# pfc-control-board.net
KiCad netlist of a schematic drawn in Altium Designer
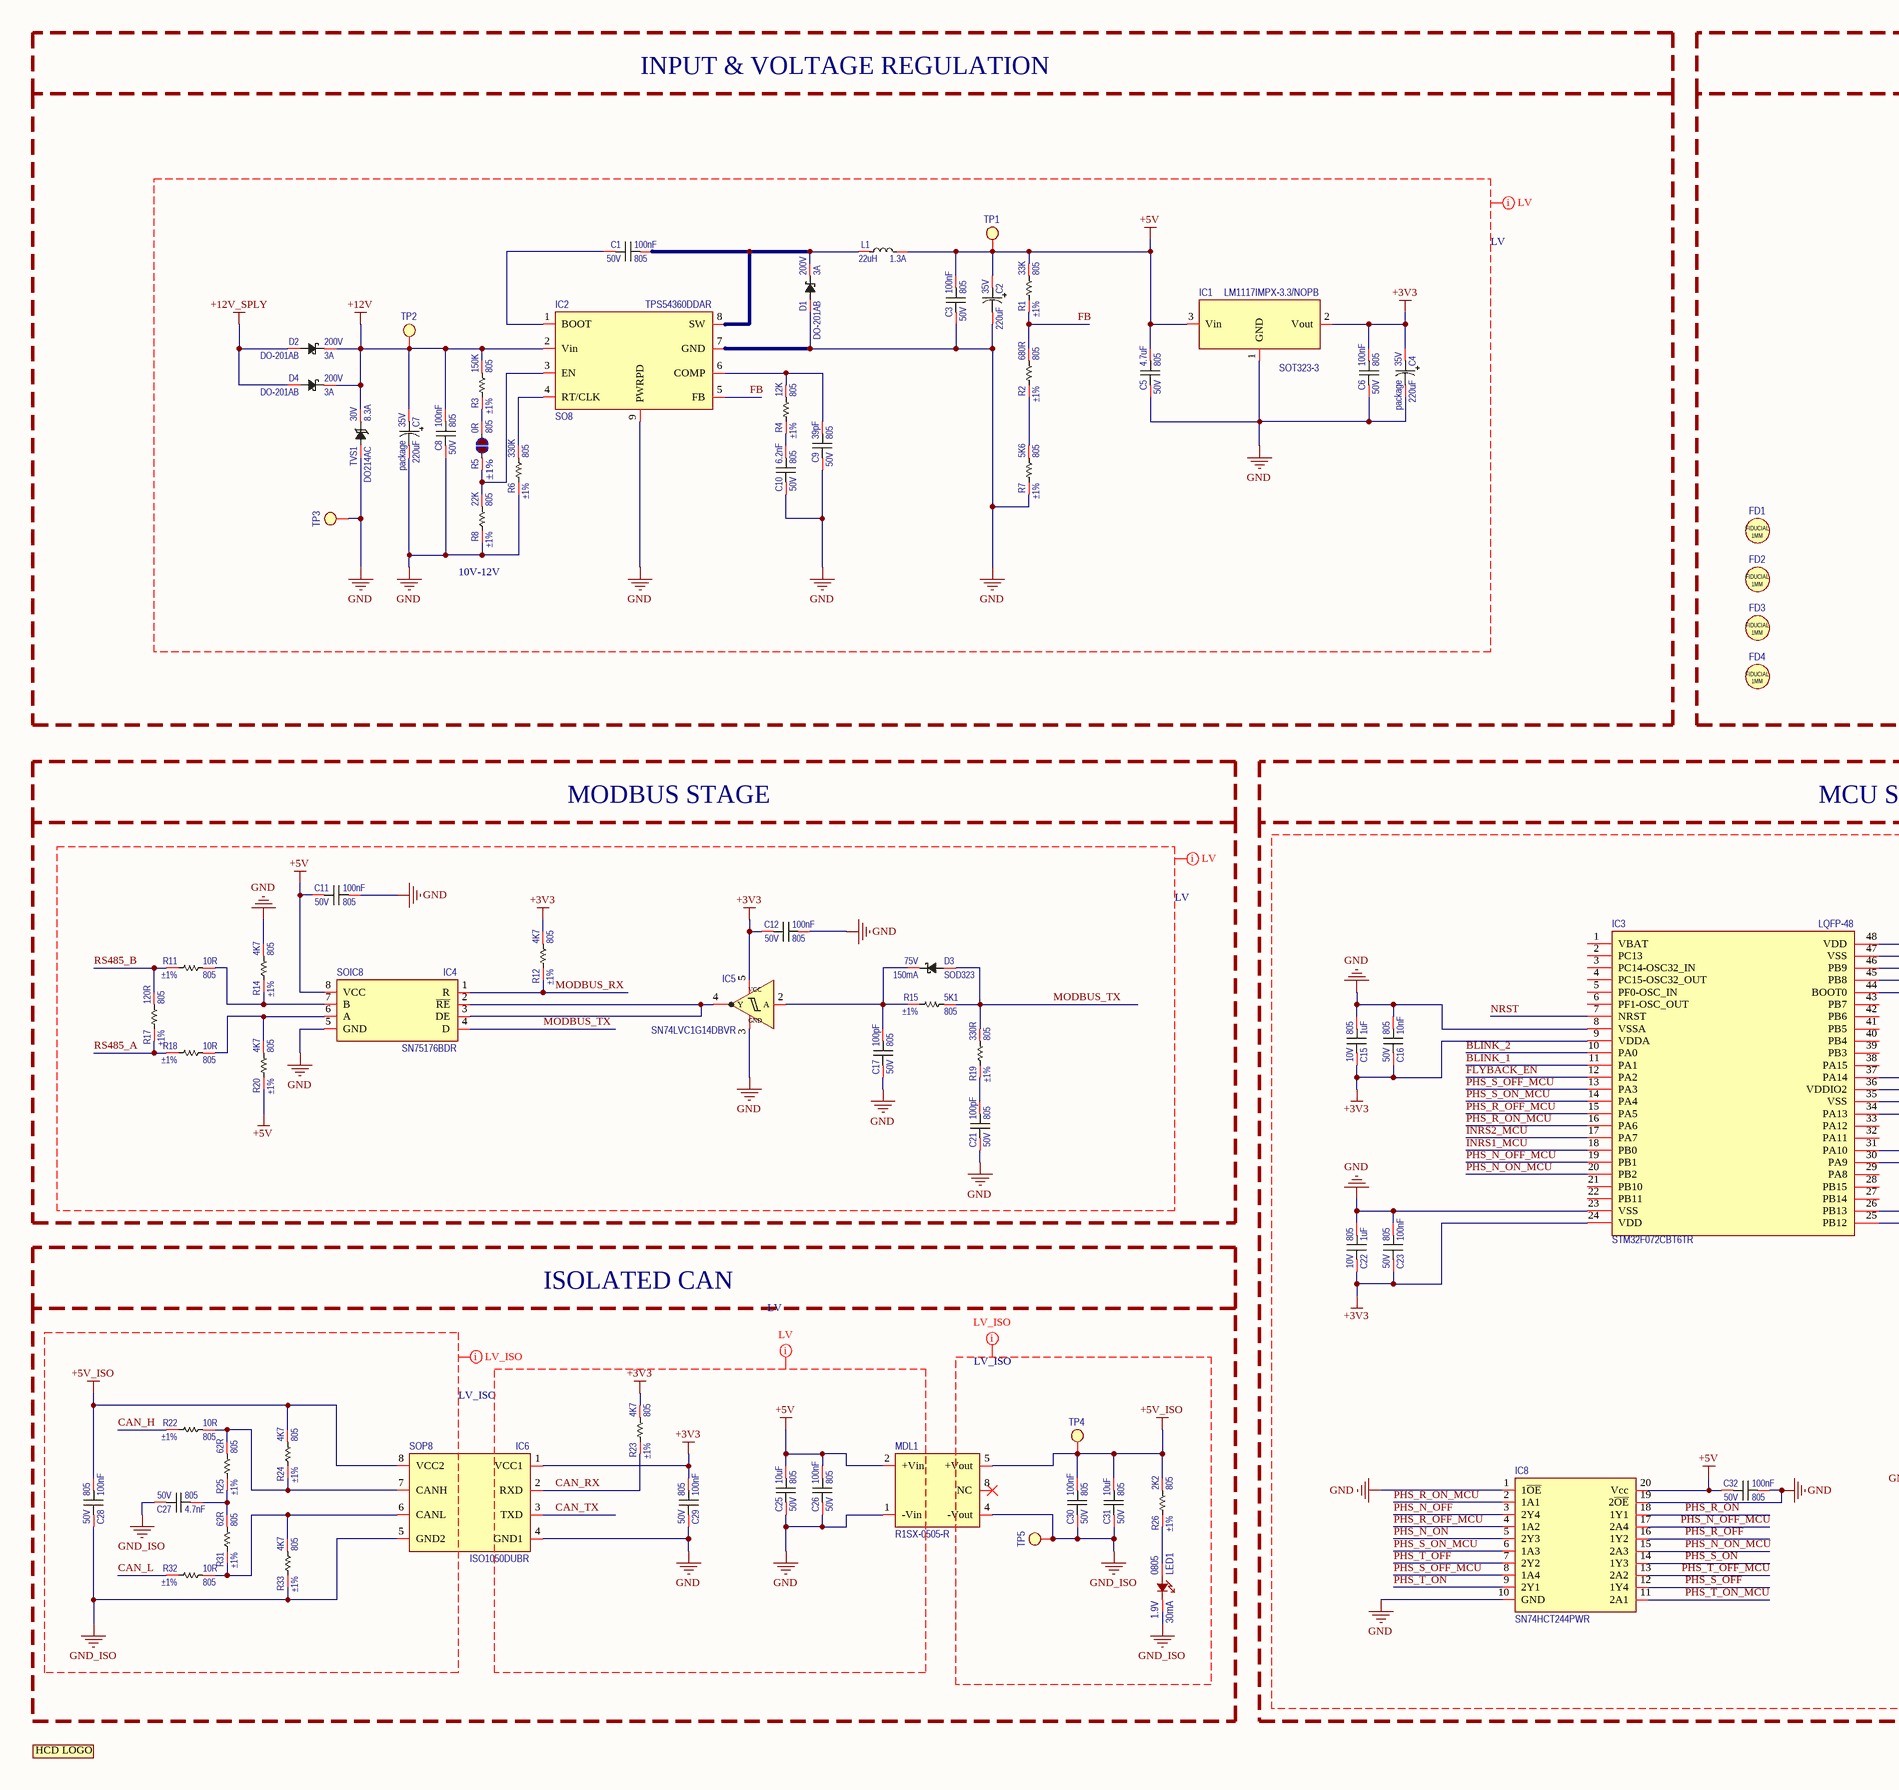
[diagram p0: pfc-control-board.SchDoc, left]
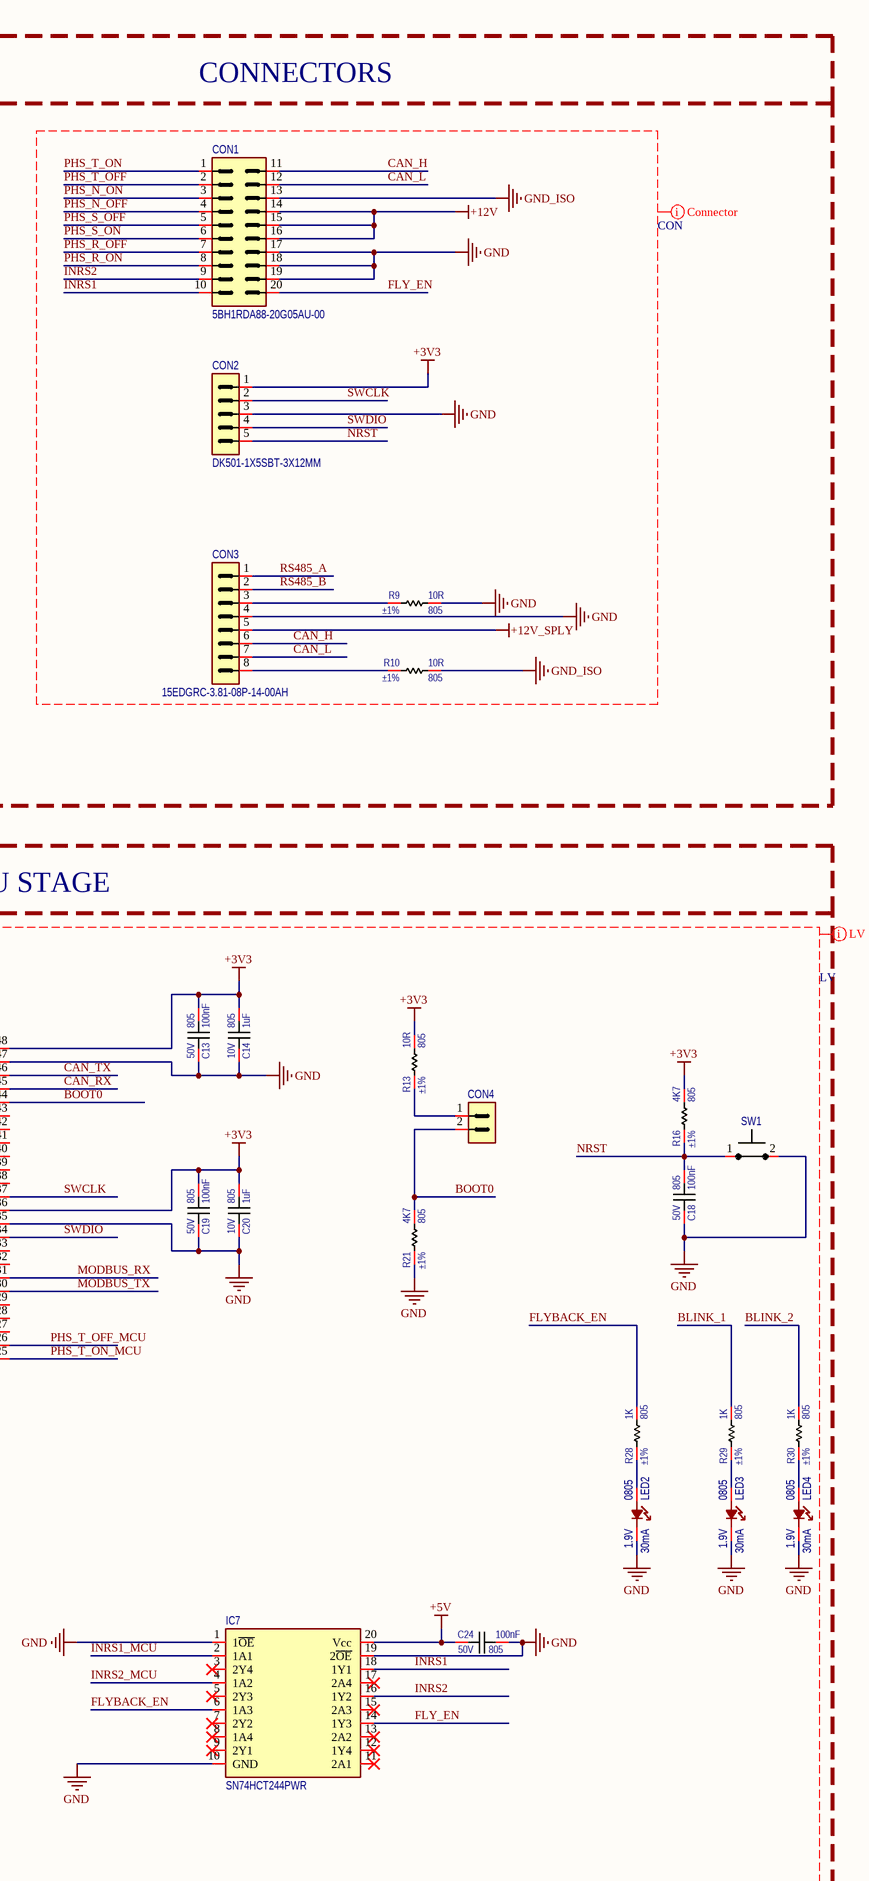
[diagram p1: pfc-control-board.SchDoc, right]

(export (version "E")
  (design (tool "Eeschema 10.0.6"))
  (components
    (comp (ref "C1")
      (value "100nF")
      (footprint "C_0805_L")
      (description "0.1 µF ±20% 50V Ceramic Capacitor X7R 0805 (2012 Metric)")
      (fields
        (field (name "VOLTAGE") "50V")
        (field (name "PACKAGE") "805")
        (field (name "TOLERANCE") "±20%")
        (field (name "MANUFACTURER") "KEMET")
      )
      (libsource (lib "HCD_Database_Libs") (part "StandardCapacitor"))
    )
    (comp (ref "C2")
      (value "220uF")
      (footprint "C_BDS35VC220MH10TP")
      (description "CAP.EL.220uF 35V 8x10 105C 2000Hrs SMD")
      (fields
        (field (name "VOLTAGE") "35V")
        (field (name "MANUFACTURER") "SAMYOUNG")
        (field (name "TOLERANCE") "±20%")
      )
      (libsource (lib "HCD_Database_Libs") (part "PolarizedCapacitor"))
    )
    (comp (ref "C3")
      (value "100nF")
      (footprint "C_0805_L")
      (description "0.1 µF ±20% 50V Ceramic Capacitor X7R 0805 (2012 Metric)")
      (fields
        (field (name "VOLTAGE") "50V")
        (field (name "PACKAGE") "805")
        (field (name "TOLERANCE") "±20%")
        (field (name "MANUFACTURER") "KEMET")
      )
      (libsource (lib "HCD_Database_Libs") (part "StandardCapacitor"))
    )
    (comp (ref "C4")
      (value "220uF")
      (footprint "C_BDS35VC220MH10TP")
      (description "CAP.EL.220uF 35V 8x10 105C 2000Hrs SMD")
      (fields
        (field (name "VOLTAGE") "35V")
        (field (name "PACKAGE") "package")
        (field (name "MANUFACTURER") "SAMYOUNG")
        (field (name "TOLERANCE") "±20%")
      )
      (libsource (lib "HCD_Database_Libs") (part "PolarizedCapacitor"))
    )
    (comp (ref "C5")
      (value "4.7uF")
      (footprint "C_0805_L")
      (description "4.7 µF ±10% 50V Ceramic Capacitor X7R 0805 (2012 Metric)")
      (fields
        (field (name "VOLTAGE") "50V")
        (field (name "PACKAGE") "805")
        (field (name "TOLERANCE") "±10%")
        (field (name "MANUFACTURER") "TDK Corporation")
      )
      (libsource (lib "HCD_Database_Libs") (part "StandardCapacitor"))
    )
    (comp (ref "C6")
      (value "100nF")
      (footprint "C_0805_L")
      (description "0.1 µF ±20% 50V Ceramic Capacitor X7R 0805 (2012 Metric)")
      (fields
        (field (name "VOLTAGE") "50V")
        (field (name "PACKAGE") "805")
        (field (name "TOLERANCE") "±20%")
        (field (name "MANUFACTURER") "KEMET")
      )
      (libsource (lib "HCD_Database_Libs") (part "StandardCapacitor"))
    )
    (comp (ref "C7")
      (value "220uF")
      (footprint "C_BDS35VC220MH10TP")
      (description "CAP.EL.220uF 35V 8x10 105C 2000Hrs SMD")
      (fields
        (field (name "VOLTAGE") "35V")
        (field (name "PACKAGE") "package")
        (field (name "MANUFACTURER") "SAMYOUNG")
        (field (name "TOLERANCE") "±20%")
      )
      (libsource (lib "HCD_Database_Libs") (part "PolarizedCapacitor"))
    )
    (comp (ref "C8")
      (value "100nF")
      (footprint "C_0805_L")
      (description "0.1 µF ±20% 50V Ceramic Capacitor X7R 0805 (2012 Metric)")
      (fields
        (field (name "VOLTAGE") "50V")
        (field (name "PACKAGE") "805")
        (field (name "TOLERANCE") "±20%")
        (field (name "MANUFACTURER") "KEMET")
      )
      (libsource (lib "HCD_Database_Libs") (part "StandardCapacitor"))
    )
    (comp (ref "C9")
      (value "39pF")
      (footprint "C_0805_L")
      (description "39 pF ±5% 50V Ceramic Capacitor C0G, NP0 0805 (2012 Metric)")
      (fields
        (field (name "VOLTAGE") "50V")
        (field (name "PACKAGE") "805")
        (field (name "TOLERANCE") "±5%")
        (field (name "MANUFACTURER") "YAGEO")
      )
      (libsource (lib "HCD_Database_Libs") (part "StandardCapacitor"))
    )
    (comp (ref "C10")
      (value "6.2nF")
      (footprint "C_0805_L")
      (description "6200 pF ±5% 50V Ceramic Capacitor C0G, NP0 0805 (2012 Metric)")
      (fields
        (field (name "VOLTAGE") "50V")
        (field (name "PACKAGE") "805")
        (field (name "MANUFACTURER") "KEMET")
        (field (name "TOLERANCE") "±5%")
      )
      (libsource (lib "HCD_Database_Libs") (part "StandardCapacitor"))
    )
    (comp (ref "C11")
      (value "100nF")
      (footprint "C_0805_L")
      (description "0.1 µF ±20% 50V Ceramic Capacitor X7R 0805 (2012 Metric)")
      (fields
        (field (name "VOLTAGE") "50V")
        (field (name "PACKAGE") "805")
        (field (name "TOLERANCE") "±20%")
        (field (name "MANUFACTURER") "KEMET")
      )
      (libsource (lib "HCD_Database_Libs") (part "StandardCapacitor"))
    )
    (comp (ref "C12")
      (value "100nF")
      (footprint "C_0805_L")
      (description "0.1 µF ±20% 50V Ceramic Capacitor X7R 0805 (2012 Metric)")
      (fields
        (field (name "VOLTAGE") "50V")
        (field (name "PACKAGE") "805")
        (field (name "TOLERANCE") "±20%")
        (field (name "MANUFACTURER") "KEMET")
      )
      (libsource (lib "HCD_Database_Libs") (part "StandardCapacitor"))
    )
    (comp (ref "C13")
      (value "100nF")
      (footprint "C_0805_L")
      (description "0.1 µF ±20% 50V Ceramic Capacitor X7R 0805 (2012 Metric)")
      (fields
        (field (name "VOLTAGE") "50V")
        (field (name "PACKAGE") "805")
        (field (name "TOLERANCE") "±20%")
        (field (name "MANUFACTURER") "KEMET")
      )
      (libsource (lib "HCD_Database_Libs") (part "StandardCapacitor"))
    )
    (comp (ref "C14")
      (value "1uF")
      (footprint "C_0805_L")
      (description "1 µF ±10% 10V Ceramic Capacitor X7R 0603 (1608 Metric)")
      (fields
        (field (name "VOLTAGE") "10V")
        (field (name "PACKAGE") "805")
        (field (name "TOLERANCE") "±10%")
        (field (name "MANUFACTURER") "Samsung Electro-Mechanics")
      )
      (libsource (lib "HCD_Database_Libs") (part "StandardCapacitor"))
    )
    (comp (ref "C15")
      (value "1uF")
      (footprint "C_0805_L")
      (description "1 µF ±10% 10V Ceramic Capacitor X7R 0603 (1608 Metric)")
      (fields
        (field (name "VOLTAGE") "10V")
        (field (name "PACKAGE") "805")
        (field (name "TOLERANCE") "±10%")
        (field (name "MANUFACTURER") "Samsung Electro-Mechanics")
      )
      (libsource (lib "HCD_Database_Libs") (part "StandardCapacitor"))
    )
    (comp (ref "C16")
      (value "10nF")
      (footprint "C_0805_L")
      (description "10000 pF ±5% 50V Ceramic Capacitor X7R 0805 (2012 Metric)")
      (fields
        (field (name "VOLTAGE") "50V")
        (field (name "PACKAGE") "805")
        (field (name "TOLERANCE") "±5 %")
        (field (name "MANUFACTURER") "KEMET")
      )
      (libsource (lib "HCD_Database_Libs") (part "StandardCapacitor"))
    )
    (comp (ref "C17")
      (value "100pF")
      (footprint "C_0805_L")
      (description "100 pF ±1% 50V Ceramic Capacitor C0G, NP0 0805 (2012 Metric)")
      (fields
        (field (name "VOLTAGE") "50V")
        (field (name "PACKAGE") "805")
        (field (name "TOLERANCE") "±1%")
        (field (name "MANUFACTURER") "KEMET")
      )
      (libsource (lib "HCD_Database_Libs") (part "StandardCapacitor"))
    )
    (comp (ref "C18")
      (value "100nF")
      (footprint "C_0805_L")
      (description "0.1 µF ±20% 50V Ceramic Capacitor X7R 0805 (2012 Metric)")
      (fields
        (field (name "VOLTAGE") "50V")
        (field (name "PACKAGE") "805")
        (field (name "TOLERANCE") "±20%")
        (field (name "MANUFACTURER") "KEMET")
      )
      (libsource (lib "HCD_Database_Libs") (part "StandardCapacitor"))
    )
    (comp (ref "C19")
      (value "100nF")
      (footprint "C_0805_L")
      (description "0.1 µF ±20% 50V Ceramic Capacitor X7R 0805 (2012 Metric)")
      (fields
        (field (name "VOLTAGE") "50V")
        (field (name "PACKAGE") "805")
        (field (name "TOLERANCE") "±20%")
        (field (name "MANUFACTURER") "KEMET")
      )
      (libsource (lib "HCD_Database_Libs") (part "StandardCapacitor"))
    )
    (comp (ref "C20")
      (value "1uF")
      (footprint "C_0805_L")
      (description "1 µF ±10% 10V Ceramic Capacitor X7R 0603 (1608 Metric)")
      (fields
        (field (name "VOLTAGE") "10V")
        (field (name "PACKAGE") "805")
        (field (name "TOLERANCE") "±10%")
        (field (name "MANUFACTURER") "Samsung Electro-Mechanics")
      )
      (libsource (lib "HCD_Database_Libs") (part "StandardCapacitor"))
    )
    (comp (ref "C21")
      (value "100pF")
      (footprint "C_0805_L")
      (description "100 pF ±1% 50V Ceramic Capacitor C0G, NP0 0805 (2012 Metric)")
      (fields
        (field (name "VOLTAGE") "50V")
        (field (name "PACKAGE") "805")
        (field (name "TOLERANCE") "±1%")
        (field (name "MANUFACTURER") "KEMET")
      )
      (libsource (lib "HCD_Database_Libs") (part "StandardCapacitor"))
    )
    (comp (ref "C22")
      (value "1uF")
      (footprint "C_0805_L")
      (description "1 µF ±10% 10V Ceramic Capacitor X7R 0603 (1608 Metric)")
      (fields
        (field (name "VOLTAGE") "10V")
        (field (name "PACKAGE") "805")
        (field (name "TOLERANCE") "±10%")
        (field (name "MANUFACTURER") "Samsung Electro-Mechanics")
      )
      (libsource (lib "HCD_Database_Libs") (part "StandardCapacitor"))
    )
    (comp (ref "C23")
      (value "100nF")
      (footprint "C_0805_L")
      (description "0.1 µF ±20% 50V Ceramic Capacitor X7R 0805 (2012 Metric)")
      (fields
        (field (name "VOLTAGE") "50V")
        (field (name "PACKAGE") "805")
        (field (name "TOLERANCE") "±20%")
        (field (name "MANUFACTURER") "KEMET")
      )
      (libsource (lib "HCD_Database_Libs") (part "StandardCapacitor"))
    )
    (comp (ref "C24")
      (value "100nF")
      (footprint "C_0805_L")
      (description "0.1 µF ±20% 50V Ceramic Capacitor X7R 0805 (2012 Metric)")
      (fields
        (field (name "VOLTAGE") "50V")
        (field (name "PACKAGE") "805")
        (field (name "TOLERANCE") "±20%")
        (field (name "MANUFACTURER") "KEMET")
      )
      (libsource (lib "HCD_Database_Libs") (part "StandardCapacitor"))
    )
    (comp (ref "C25")
      (value "10uF")
      (footprint "C_0805_L")
      (description "10 µF ±10% 50V Ceramic Capacitor X5R 0805 (2012 Metric)")
      (fields
        (field (name "VOLTAGE") "50V")
        (field (name "PACKAGE") "805")
        (field (name "TOLERANCE") "±10%")
        (field (name "MANUFACTURER") "Murata Electronics")
      )
      (libsource (lib "HCD_Database_Libs") (part "StandardCapacitor"))
    )
    (comp (ref "C26")
      (value "100nF")
      (footprint "C_0805_L")
      (description "0.1 µF ±20% 50V Ceramic Capacitor X7R 0805 (2012 Metric)")
      (fields
        (field (name "VOLTAGE") "50V")
        (field (name "PACKAGE") "805")
        (field (name "TOLERANCE") "±20%")
        (field (name "MANUFACTURER") "KEMET")
      )
      (libsource (lib "HCD_Database_Libs") (part "StandardCapacitor"))
    )
    (comp (ref "C27")
      (value "4.7nF")
      (footprint "C_0805_L")
      (description "4700 pF ±10% 50V Ceramic Capacitor X7R 0805 (2012 Metric)")
      (fields
        (field (name "VOLTAGE") "50V")
        (field (name "PACKAGE") "805")
        (field (name "TOLERANCE") "±10%")
        (field (name "MANUFACTURER") "KEMET")
      )
      (libsource (lib "HCD_Database_Libs") (part "StandardCapacitor"))
    )
    (comp (ref "C28")
      (value "100nF")
      (footprint "C_0805_L")
      (description "0.1 µF ±20% 50V Ceramic Capacitor X7R 0805 (2012 Metric)")
      (fields
        (field (name "VOLTAGE") "50V")
        (field (name "PACKAGE") "805")
        (field (name "TOLERANCE") "±20%")
        (field (name "MANUFACTURER") "KEMET")
      )
      (libsource (lib "HCD_Database_Libs") (part "StandardCapacitor"))
    )
    (comp (ref "C29")
      (value "100nF")
      (footprint "C_0805_L")
      (description "0.1 µF ±20% 50V Ceramic Capacitor X7R 0805 (2012 Metric)")
      (fields
        (field (name "VOLTAGE") "50V")
        (field (name "PACKAGE") "805")
        (field (name "TOLERANCE") "±20%")
        (field (name "MANUFACTURER") "KEMET")
      )
      (libsource (lib "HCD_Database_Libs") (part "StandardCapacitor"))
    )
    (comp (ref "C30")
      (value "100nF")
      (footprint "C_0805_L")
      (description "0.1 µF ±20% 50V Ceramic Capacitor X7R 0805 (2012 Metric)")
      (fields
        (field (name "VOLTAGE") "50V")
        (field (name "PACKAGE") "805")
        (field (name "TOLERANCE") "±20%")
        (field (name "MANUFACTURER") "KEMET")
      )
      (libsource (lib "HCD_Database_Libs") (part "StandardCapacitor"))
    )
    (comp (ref "C31")
      (value "10uF")
      (footprint "C_0805_L")
      (description "10 µF ±10% 50V Ceramic Capacitor X5R 0805 (2012 Metric)")
      (fields
        (field (name "VOLTAGE") "50V")
        (field (name "PACKAGE") "805")
        (field (name "TOLERANCE") "±10%")
        (field (name "MANUFACTURER") "Murata Electronics")
      )
      (libsource (lib "HCD_Database_Libs") (part "StandardCapacitor"))
    )
    (comp (ref "C32")
      (value "100nF")
      (footprint "C_0805_L")
      (description "0.1 µF ±20% 50V Ceramic Capacitor X7R 0805 (2012 Metric)")
      (fields
        (field (name "VOLTAGE") "50V")
        (field (name "PACKAGE") "805")
        (field (name "TOLERANCE") "±20%")
        (field (name "MANUFACTURER") "KEMET")
      )
      (libsource (lib "HCD_Database_Libs") (part "StandardCapacitor"))
    )
    (comp (ref "CON1")
      (value "CON_20POS_2R")
      (footprint "male-thd-box-header-2x10-2.54mm-90D_AMTEK")
      (description "BOX HEADER 20PIN(2x10) 2.54mm THT R/A MALE BLACK")
      (fields
        (field (name "MANUFACTURER PN") "5BH1RDA88-20G05AU-00")
        (field (name "MANUFACTURER") "AMTEK")
        (field (name "VOLTAGE") "1000V AC")
      )
      (libsource (lib "HCD_Database_Libs") (part "CON_20POS_2R"))
    )
    (comp (ref "CON2")
      (value "CON_5POS_1R")
      (footprint "male-thd-1x5-pin-header-2.54mm-180D")
      (description "PIN HEADER 5PIN(1x5) 2.54mm THT V/T 3X12MM")
      (fields
        (field (name "MANUFACTURER PN") "DK501-1X5SBT-3X12MM")
        (field (name "MANUFACTURER") "DENK-ELEC")
        (field (name "VOLTAGE") "1000V AC")
      )
      (libsource (lib "HCD_Database_Libs") (part "CON_5POS_1R"))
    )
    (comp (ref "CON3")
      (value "CON_8POS_1R")
      (footprint "CON_15EDGRC-3.81-08P-14-00AH")
      (description "TERM.BLK.3.81MM 8P 90C MALE GREEN CLOSED")
      (fields
        (field (name "MANUFACTURER PN") "15EDGRC-3.81-08P-14-00AH")
        (field (name "MANUFACTURER") "DEGSON")
        (field (name "VOLTAGE") "300V")
      )
      (libsource (lib "HCD_Database_Libs") (part "CON_8POS_1R"))
    )
    (comp (ref "CON4")
      (value "CON_2POS_1R")
      (footprint "male-thd-1x2-pin-header-2.54mm-90D")
      (description "PIN HEADER 2PIN(1x2) 2.54mm THT R/A 6X3X4.5MM")
      (fields (field (name "MANUFACTURER") "AMTEK") (field (name "VOLTAGE") "500V AC"))
      (libsource (lib "HCD_Database_Libs") (part "CON_2POS_1R"))
    )
    (comp (ref "D1")
      (value "SchDiode_A1C2")
      (footprint "D_DO214AB_ONSEMI")
      (description "DIODE FAST RECOVERY Single 3A 200V DO214AB (SMC)")
      (fields
        (field (name "VOLTAGE") "200V")
        (field (name "CURRENT") "3A")
        (field (name "PACKAGE") "DO-201AB")
        (field (name "MANUFACTURER") "ONS (FAIRCHILD)")
      )
      (libsource (lib "HCD_Database_Libs") (part "SchDiode_A1C2"))
    )
    (comp (ref "D2")
      (value "SchDiode_A1C2")
      (footprint "D_DO214AB_ONSEMI")
      (description "DIODE FAST RECOVERY Single 3A 200V DO214AB (SMC)")
      (fields
        (field (name "VOLTAGE") "200V")
        (field (name "CURRENT") "3A")
        (field (name "PACKAGE") "DO-201AB")
        (field (name "MANUFACTURER") "ONS (FAIRCHILD)")
      )
      (libsource (lib "HCD_Database_Libs") (part "SchDiode_A1C2"))
    )
    (comp (ref "D3")
      (value "SchDiode_A1C2")
      (footprint "D_SOD323_HOTTECH")
      (description "DIODE FAST SWITCHING Single 150mA 75V SMT SOD323")
      (fields
        (field (name "VOLTAGE") "75V")
        (field (name "CURRENT") "150mA")
        (field (name "PACKAGE") "SOD323")
        (field (name "MANUFACTURER") "HOTTECH")
      )
      (libsource (lib "HCD_Database_Libs") (part "SchDiode_A1C2"))
    )
    (comp (ref "D4")
      (value "SchDiode_A1C2")
      (footprint "D_DO214AB_ONSEMI")
      (description "DIODE FAST RECOVERY Single 3A 200V DO214AB (SMC)")
      (fields
        (field (name "VOLTAGE") "200V")
        (field (name "CURRENT") "3A")
        (field (name "PACKAGE") "DO-201AB")
        (field (name "MANUFACTURER") "ONS (FAIRCHILD)")
      )
      (libsource (lib "HCD_Database_Libs") (part "SchDiode_A1C2"))
    )
    (comp (ref "FD1")
      (value "~")
      (footprint "FIDUCIAL_1MM")
      (description "Fiducial 1mm")
      (libsource (lib "HCD_Database_Libs") (part "FIDUCIAL_1MM_NO_BOM"))
    )
    (comp (ref "FD2")
      (value "~")
      (footprint "FIDUCIAL_1MM")
      (description "Fiducial 1mm")
      (libsource (lib "HCD_Database_Libs") (part "FIDUCIAL_1MM_NO_BOM"))
    )
    (comp (ref "FD3")
      (value "~")
      (footprint "FIDUCIAL_1MM")
      (description "Fiducial 1mm")
      (libsource (lib "HCD_Database_Libs") (part "FIDUCIAL_1MM_NO_BOM"))
    )
    (comp (ref "FD4")
      (value "~")
      (footprint "FIDUCIAL_1MM")
      (description "Fiducial 1mm")
      (libsource (lib "HCD_Database_Libs") (part "FIDUCIAL_1MM_NO_BOM"))
    )
    (comp (ref "IC1")
      (value "IC_LDO_LDL1117")
      (footprint "IC_SOT223_TEXAS")
      (description "IC REG LIN 3.3V 800MA SOT223-4")
      (fields
        (field (name "MANUFACTURER PN") "LM1117IMPX-3.3/NOPB")
        (field (name "PACKAGE") "SOT323-3")
        (field (name "MANUFACTURER") "Texas Instruments")
        (field (name "VOLTAGE") "15V to 20V")
      )
      (libsource (lib "HCD_Database_Libs") (part "IC_LDO_LDL1117"))
    )
    (comp (ref "IC2")
      (value "IC_SWREG_TPS54360DDAR")
      (footprint "IC_SO8_TEXAS")
      (description "IC-54360 REG BUCK SPLIT RAIL 8SOPWRPAD")
      (fields
        (field (name "MANUFACTURER PN") "TPS54360DDAR")
        (field (name "PACKAGE") "SO8")
        (field (name "MANUFACTURER") "Texas Instruments")
        (field (name "VOLTAGE") "4V5 to 60V")
      )
      (libsource (lib "HCD_Database_Libs") (part "IC_SWREG_TPS54360DDAR"))
    )
    (comp (ref "IC3")
      (value "IC_STM32F072CBT6TR")
      (footprint "IC_LQFP48_ST")
      (description "IC-32F072C MCU 32BIT 128KB FLASH 48LQFP")
      (fields
        (field (name "MANUFACTURER PN") "STM32F072CBT6TR")
        (field (name "PACKAGE") "LQFP-48")
        (field (name "MANUFACTURER") "STMicroelectronics")
        (field (name "VOLTAGE") "-0.3V to 4V")
      )
      (libsource (lib "HCD_Database_Libs") (part "IC_STM32F072CBT6TR"))
    )
    (comp (ref "IC4")
      (value "IC_TR_SN75176BDR")
      (footprint "IC_SOIC8-D_TEXAS")
      (description "IC-75176 RS485 DRIVER SMD SO8 TR TI")
      (fields
        (field (name "MANUFACTURER PN") "SN75176BDR")
        (field (name "PACKAGE") "SOIC8")
        (field (name "MANUFACTURER") "Texas Instruments")
        (field (name "VOLTAGE") "0V to 7V")
      )
      (libsource (lib "HCD_Database_Libs") (part "IC_TR_SN75176BDR"))
    )
    (comp (ref "IC5")
      (value "IC_BUF_NON_A2-3GND-4Y-5VCC")
      (footprint "IC_SOT23-5_TEXAS")
      (description "IC-74LVC14 BUFFER SCHMIT TRIG SOT23-5 SMD")
      (fields
        (field (name "MANUFACTURER PN") "SN74LVC1G14DBVR")
        (field (name "MANUFACTURER") "Texas Instruments")
        (field (name "VOLTAGE") "-0V5 to 6V5")
      )
      (libsource (lib "HCD_Database_Libs") (part "IC_BUF_NON_A2-3GND-4Y-5VCC"))
    )
    (comp (ref "IC6")
      (value "IC_TR_ISO1050DUBR")
      (footprint "IC_SOP8_TEXAS")
      (description "IC-1050DUBR ISOLATED CAN TRANSCEIVER SOP8 SMD TI")
      (fields
        (field (name "MANUFACTURER PN") "ISO1050DUBR")
        (field (name "PACKAGE") "SOP8")
        (field (name "MANUFACTURER") "Texas Instruments")
        (field (name "VOLTAGE") "-0V5 to 6V")
      )
      (libsource (lib "HCD_Database_Libs") (part "IC_TR_ISO1050DUBR"))
    )
    (comp (ref "IC7")
      (value "IC_BUF_SN74HCT244PWR")
      (footprint "IC_TSSOP20_TEXAS")
      (description "IC-74HCT244 SMD TSSOP20")
      (fields
        (field (name "MANUFACTURER PN") "SN74HCT244PWR")
        (field (name "MANUFACTURER") "Texas Instruments")
        (field (name "VOLTAGE") "-0V5 to 7V")
      )
      (libsource (lib "HCD_Database_Libs") (part "IC_BUF_SN74HCT244PWR"))
    )
    (comp (ref "IC8")
      (value "IC_BUF_SN74HCT244PWR")
      (footprint "IC_TSSOP20_TEXAS")
      (description "IC-74HCT244 SMD TSSOP20")
      (fields
        (field (name "MANUFACTURER PN") "SN74HCT244PWR")
        (field (name "MANUFACTURER") "Texas Instruments")
        (field (name "VOLTAGE") "-0V5 to 7V")
      )
      (libsource (lib "HCD_Database_Libs") (part "IC_BUF_SN74HCT244PWR"))
    )
    (comp (ref "L1")
      (value "22uH")
      (footprint "IND_NR6028")
      (description "INDUCTOR POWER 22UH 6X6MM 1.44A SMD")
      (fields
        (field (name "CURRENT") "1.3A")
        (field (name "MANUFACTURER") "Core Master")
        (field (name "TOLERANCE") "±20%")
      )
      (libsource (lib "HCD_Database_Libs") (part "StandardInductor"))
    )
    (comp (ref "LED1")
      (value "LED_RED")
      (footprint "LED_0805")
      (description "LED SMD 0805 RED 110mcd 120° WATER CLEAR")
      (fields
        (field (name "VOLTAGE") "1.9V")
        (field (name "CURRENT") "30mA")
        (field (name "PACKAGE") "0805")
        (field (name "MANUFACTURER") "HONGLITRONIC")
      )
      (libsource (lib "HCD_Database_Libs") (part "LED_RED"))
    )
    (comp (ref "LED2")
      (value "LED_RED")
      (footprint "LED_0805")
      (description "LED SMD 0805 RED 110mcd 120° WATER CLEAR")
      (fields
        (field (name "VOLTAGE") "1.9V")
        (field (name "CURRENT") "30mA")
        (field (name "PACKAGE") "0805")
        (field (name "MANUFACTURER") "HONGLITRONIC")
      )
      (libsource (lib "HCD_Database_Libs") (part "LED_RED"))
    )
    (comp (ref "LED3")
      (value "LED_RED")
      (footprint "LED_0805")
      (description "LED SMD 0805 RED 110mcd 120° WATER CLEAR")
      (fields
        (field (name "VOLTAGE") "1.9V")
        (field (name "CURRENT") "30mA")
        (field (name "PACKAGE") "0805")
        (field (name "MANUFACTURER") "HONGLITRONIC")
      )
      (libsource (lib "HCD_Database_Libs") (part "LED_RED"))
    )
    (comp (ref "LED4")
      (value "LED_RED")
      (footprint "LED_0805")
      (description "LED SMD 0805 RED 110mcd 120° WATER CLEAR")
      (fields
        (field (name "VOLTAGE") "1.9V")
        (field (name "CURRENT") "30mA")
        (field (name "PACKAGE") "0805")
        (field (name "MANUFACTURER") "HONGLITRONIC")
      )
      (libsource (lib "HCD_Database_Libs") (part "LED_RED"))
    )
    (comp (ref "LOGO1")
      (value "HCD_LOGO")
      (footprint "HCD_LOGO_V1")
      (description "Hamit Can Dinç LOGO")
      (libsource (lib "HCD_Database_Libs") (part "HCD_LOGO"))
    )
    (comp (ref "MDL1")
      (value "DCDC_Module_Recom_R1SX")
      (footprint "DCDC_R1SX-0505-R")
      (description "DC/DC CONV 1W 5VDC 5VDC 200mA Op Fr")
      (fields
        (field (name "MANUFACTURER PN") "R1SX-0505-R")
        (field (name "MANUFACTURER") "Recom Power")
        (field (name "VOLTAGE") "ADJ")
      )
      (libsource (lib "HCD_Database_Libs") (part "DCDC_Module_Recom_R1SX"))
    )
    (comp (ref "R1")
      (value "33K")
      (footprint "R_0805_L")
      (description "33 kOhms ±1% 0.25W, 1/4W Chip Resistor 0805 (2012 Metric) Automotive AEC-Q200 Thick Film")
      (fields
        (field (name "TOLERANCE") "±1%")
        (field (name "PACKAGE") "805")
        (field (name "MANUFACTURER") "KOA Speer Electronics, Inc.")
        (field (name "POWER") "0,125W")
      )
      (libsource (lib "HCD_Database_Libs") (part "StandardResistor"))
    )
    (comp (ref "R2")
      (value "680R")
      (footprint "R_0805_L")
      (description "680 Ohms ±1% 0.25W, 1/4W Chip Resistor 0805 (2012 Metric) Automotive AEC-Q200 Thick Film")
      (fields
        (field (name "TOLERANCE") "±1%")
        (field (name "PACKAGE") "805")
        (field (name "MANUFACTURER") "Rohm Semiconductor")
        (field (name "POWER") "0,125W")
      )
      (libsource (lib "HCD_Database_Libs") (part "StandardResistor"))
    )
    (comp (ref "R3")
      (value "150K")
      (footprint "R_0805_L")
      (description "150 kOhms ±1% 0.125W, 1/8W Chip Resistor 0805 (2012 Metric) Moisture Resistant Thick Film")
      (fields
        (field (name "TOLERANCE") "±1%")
        (field (name "PACKAGE") "805")
        (field (name "MANUFACTURER") "YAGEO")
        (field (name "POWER") "0,125W")
      )
      (libsource (lib "HCD_Database_Libs") (part "StandardResistor"))
    )
    (comp (ref "R4")
      (value "12K")
      (footprint "R_0805_L")
      (fields
        (field (name "TOLERANCE") "±1%")
        (field (name "PACKAGE") "805")
        (field (name "MANUFACTURER") "KOA Speer Electronics, Inc.")
        (field (name "POWER") "0,125W")
        (field (name "Comment") "StandardResistor")
      )
      (libsource (lib "HCD_Database_Libs") (part "StandardResistor"))
    )
    (comp (ref "R5")
      (value "0R")
      (footprint "R_0805_L")
      (description "0 Ohms Jumper Chip Resistor 0805 (2012 Metric) Moisture Resistant Thick Film")
      (fields
        (field (name "TOLERANCE") "±1%")
        (field (name "PACKAGE") "805")
        (field (name "MANUFACTURER") "YAGEO")
        (field (name "POWER") "0,125W")
      )
      (libsource (lib "HCD_Database_Libs") (part "Jumper"))
    )
    (comp (ref "R6")
      (value "330K")
      (footprint "R_0805_L")
      (description "330 kOhms ±1% 0.125W, 1/8W Chip Resistor 0805 (2012 Metric) Moisture Resistant Thick Film")
      (fields
        (field (name "TOLERANCE") "±1%")
        (field (name "PACKAGE") "805")
        (field (name "MANUFACTURER") "YAGEO")
        (field (name "POWER") "0,125W")
      )
      (libsource (lib "HCD_Database_Libs") (part "StandardResistor"))
    )
    (comp (ref "R7")
      (value "5K6")
      (footprint "R_0805_L")
      (description "5.6 kOhms ±1% 0.25W, 1/4W Chip Resistor 0805 (2012 Metric) Automotive AEC-Q200 Thick Film")
      (fields
        (field (name "TOLERANCE") "±1%")
        (field (name "PACKAGE") "805")
        (field (name "MANUFACTURER") "Rohm Semiconductor")
        (field (name "POWER") "0,125W")
      )
      (libsource (lib "HCD_Database_Libs") (part "StandardResistor"))
    )
    (comp (ref "R8")
      (value "22K")
      (footprint "R_0805_L")
      (description "22 kOhms ±1% 0.25W, 1/4W Chip Resistor 0805 (2012 Metric) Automotive AEC-Q200 Thick Film")
      (fields
        (field (name "TOLERANCE") "±1%")
        (field (name "PACKAGE") "805")
        (field (name "MANUFACTURER") "Rohm Semiconductor")
        (field (name "POWER") "0,125W")
      )
      (libsource (lib "HCD_Database_Libs") (part "StandardResistor"))
    )
    (comp (ref "R9")
      (value "10R")
      (footprint "R_0805_L")
      (description "10 Ohms ±1% 0.125W, 1/8W Chip Resistor 0805 (2012 Metric) Moisture Resistant Thick Film")
      (fields
        (field (name "TOLERANCE") "±1%")
        (field (name "PACKAGE") "805")
        (field (name "MANUFACTURER") "YAGEO")
        (field (name "POWER") "0,125W")
      )
      (libsource (lib "HCD_Database_Libs") (part "StandardResistor"))
    )
    (comp (ref "R10")
      (value "10R")
      (footprint "R_0805_L")
      (description "10 Ohms ±1% 0.125W, 1/8W Chip Resistor 0805 (2012 Metric) Moisture Resistant Thick Film")
      (fields
        (field (name "TOLERANCE") "±1%")
        (field (name "PACKAGE") "805")
        (field (name "MANUFACTURER") "YAGEO")
        (field (name "POWER") "0,125W")
      )
      (libsource (lib "HCD_Database_Libs") (part "StandardResistor"))
    )
    (comp (ref "R11")
      (value "10R")
      (footprint "R_0805_L")
      (description "10 Ohms ±1% 0.125W, 1/8W Chip Resistor 0805 (2012 Metric) Moisture Resistant Thick Film")
      (fields
        (field (name "TOLERANCE") "±1%")
        (field (name "PACKAGE") "805")
        (field (name "MANUFACTURER") "YAGEO")
        (field (name "POWER") "0,125W")
      )
      (libsource (lib "HCD_Database_Libs") (part "StandardResistor"))
    )
    (comp (ref "R12")
      (value "4K7")
      (footprint "R_0805_L")
      (description "4.7 kOhms ±1% 0.125W, 1/8W Chip Resistor 0805 (2012 Metric) Moisture Resistant Thick Film")
      (fields
        (field (name "TOLERANCE") "±1%")
        (field (name "PACKAGE") "805")
        (field (name "MANUFACTURER") "YAGEO")
        (field (name "POWER") "0,125W")
      )
      (libsource (lib "HCD_Database_Libs") (part "StandardResistor"))
    )
    (comp (ref "R13")
      (value "10R")
      (footprint "R_0805_L")
      (description "10 Ohms ±1% 0.125W, 1/8W Chip Resistor 0805 (2012 Metric) Moisture Resistant Thick Film")
      (fields
        (field (name "TOLERANCE") "±1%")
        (field (name "PACKAGE") "805")
        (field (name "MANUFACTURER") "YAGEO")
        (field (name "POWER") "0,125W")
      )
      (libsource (lib "HCD_Database_Libs") (part "StandardResistor"))
    )
    (comp (ref "R14")
      (value "4K7")
      (footprint "R_0805_L")
      (description "4.7 kOhms ±1% 0.125W, 1/8W Chip Resistor 0805 (2012 Metric) Moisture Resistant Thick Film")
      (fields
        (field (name "TOLERANCE") "±1%")
        (field (name "PACKAGE") "805")
        (field (name "MANUFACTURER") "YAGEO")
        (field (name "POWER") "0,125W")
      )
      (libsource (lib "HCD_Database_Libs") (part "StandardResistor"))
    )
    (comp (ref "R15")
      (value "5K1")
      (footprint "R_0805_L")
      (description "5.1 kOhms ±1% 0.25W, 1/4W Chip Resistor 0805 (2012 Metric) Moisture Resistant Thick Film")
      (fields
        (field (name "TOLERANCE") "±1%")
        (field (name "PACKAGE") "805")
        (field (name "MANUFACTURER") "YAGEO")
        (field (name "POWER") "0,125W")
      )
      (libsource (lib "HCD_Database_Libs") (part "StandardResistor"))
    )
    (comp (ref "R16")
      (value "4K7")
      (footprint "R_0805_L")
      (description "4.7 kOhms ±1% 0.125W, 1/8W Chip Resistor 0805 (2012 Metric) Moisture Resistant Thick Film")
      (fields
        (field (name "TOLERANCE") "±1%")
        (field (name "PACKAGE") "805")
        (field (name "MANUFACTURER") "YAGEO")
        (field (name "POWER") "0,125W")
      )
      (libsource (lib "HCD_Database_Libs") (part "StandardResistor"))
    )
    (comp (ref "R17")
      (value "120R")
      (footprint "R_0805_L")
      (description "120 Ohms ±1% 0.25W, 1/4W Chip Resistor 0805 (2012 Metric) Moisture Resistant Thick Film")
      (fields
        (field (name "TOLERANCE") "±1%")
        (field (name "PACKAGE") "805")
        (field (name "MANUFACTURER") "YAGEO")
        (field (name "POWER") "0,125W")
      )
      (libsource (lib "HCD_Database_Libs") (part "StandardResistor"))
    )
    (comp (ref "R18")
      (value "10R")
      (footprint "R_0805_L")
      (description "10 Ohms ±1% 0.125W, 1/8W Chip Resistor 0805 (2012 Metric) Moisture Resistant Thick Film")
      (fields
        (field (name "TOLERANCE") "±1%")
        (field (name "PACKAGE") "805")
        (field (name "MANUFACTURER") "YAGEO")
        (field (name "POWER") "0,125W")
      )
      (libsource (lib "HCD_Database_Libs") (part "StandardResistor"))
    )
    (comp (ref "R19")
      (value "330R")
      (footprint "R_0805_L")
      (description "330 Ohms ±1% 0.25W, 1/4W Chip Resistor 0805 (2012 Metric) Moisture Resistant Thick Film")
      (fields
        (field (name "TOLERANCE") "±1%")
        (field (name "PACKAGE") "805")
        (field (name "MANUFACTURER") "YAGEO")
        (field (name "POWER") "0,125W")
      )
      (libsource (lib "HCD_Database_Libs") (part "StandardResistor"))
    )
    (comp (ref "R20")
      (value "4K7")
      (footprint "R_0805_L")
      (description "4.7 kOhms ±1% 0.125W, 1/8W Chip Resistor 0805 (2012 Metric) Moisture Resistant Thick Film")
      (fields
        (field (name "TOLERANCE") "±1%")
        (field (name "PACKAGE") "805")
        (field (name "MANUFACTURER") "YAGEO")
        (field (name "POWER") "0,125W")
      )
      (libsource (lib "HCD_Database_Libs") (part "StandardResistor"))
    )
    (comp (ref "R21")
      (value "4K7")
      (footprint "R_0805_L")
      (description "4.7 kOhms ±1% 0.125W, 1/8W Chip Resistor 0805 (2012 Metric) Moisture Resistant Thick Film")
      (fields
        (field (name "TOLERANCE") "±1%")
        (field (name "PACKAGE") "805")
        (field (name "MANUFACTURER") "YAGEO")
        (field (name "POWER") "0,125W")
      )
      (libsource (lib "HCD_Database_Libs") (part "StandardResistor"))
    )
    (comp (ref "R22")
      (value "10R")
      (footprint "R_0805_L")
      (description "10 Ohms ±1% 0.125W, 1/8W Chip Resistor 0805 (2012 Metric) Moisture Resistant Thick Film")
      (fields
        (field (name "TOLERANCE") "±1%")
        (field (name "PACKAGE") "805")
        (field (name "MANUFACTURER") "YAGEO")
        (field (name "POWER") "0,125W")
      )
      (libsource (lib "HCD_Database_Libs") (part "StandardResistor"))
    )
    (comp (ref "R23")
      (value "4K7")
      (footprint "R_0805_L")
      (description "4.7 kOhms ±1% 0.125W, 1/8W Chip Resistor 0805 (2012 Metric) Moisture Resistant Thick Film")
      (fields
        (field (name "TOLERANCE") "±1%")
        (field (name "PACKAGE") "805")
        (field (name "MANUFACTURER") "YAGEO")
        (field (name "POWER") "0,125W")
      )
      (libsource (lib "HCD_Database_Libs") (part "StandardResistor"))
    )
    (comp (ref "R24")
      (value "4K7")
      (footprint "R_0805_L")
      (description "4.7 kOhms ±1% 0.125W, 1/8W Chip Resistor 0805 (2012 Metric) Moisture Resistant Thick Film")
      (fields
        (field (name "TOLERANCE") "±1%")
        (field (name "PACKAGE") "805")
        (field (name "MANUFACTURER") "YAGEO")
        (field (name "POWER") "0,125W")
      )
      (libsource (lib "HCD_Database_Libs") (part "StandardResistor"))
    )
    (comp (ref "R25")
      (value "62R")
      (footprint "R_0805_L")
      (fields
        (field (name "TOLERANCE") "±1%")
        (field (name "PACKAGE") "805")
        (field (name "MANUFACTURER") "YAGEO")
        (field (name "POWER") "0,125W")
        (field (name "Comment") "StandardResistor")
      )
      (libsource (lib "HCD_Database_Libs") (part "StandardResistor"))
    )
    (comp (ref "R26")
      (value "2K2")
      (footprint "R_0805_L")
      (fields
        (field (name "TOLERANCE") "±1%")
        (field (name "PACKAGE") "805")
        (field (name "MANUFACTURER") "YAGEO")
        (field (name "POWER") "0,125W")
        (field (name "Comment") "StandardResistor")
      )
      (libsource (lib "HCD_Database_Libs") (part "StandardResistor"))
    )
    (comp (ref "R28")
      (value "1K")
      (footprint "R_0805_L")
      (description "1 kOhms ±1% 0.125W, 1/8W Chip Resistor 0805 (2012 Metric) Moisture Resistant Thick Film")
      (fields
        (field (name "TOLERANCE") "±1%")
        (field (name "PACKAGE") "805")
        (field (name "MANUFACTURER") "YAGEO")
        (field (name "POWER") "0,125W")
      )
      (libsource (lib "HCD_Database_Libs") (part "StandardResistor"))
    )
    (comp (ref "R29")
      (value "1K")
      (footprint "R_0805_L")
      (description "1 kOhms ±1% 0.125W, 1/8W Chip Resistor 0805 (2012 Metric) Moisture Resistant Thick Film")
      (fields
        (field (name "TOLERANCE") "±1%")
        (field (name "PACKAGE") "805")
        (field (name "MANUFACTURER") "YAGEO")
        (field (name "POWER") "0,125W")
      )
      (libsource (lib "HCD_Database_Libs") (part "StandardResistor"))
    )
    (comp (ref "R30")
      (value "1K")
      (footprint "R_0805_L")
      (description "1 kOhms ±1% 0.125W, 1/8W Chip Resistor 0805 (2012 Metric) Moisture Resistant Thick Film")
      (fields
        (field (name "TOLERANCE") "±1%")
        (field (name "PACKAGE") "805")
        (field (name "MANUFACTURER") "YAGEO")
        (field (name "POWER") "0,125W")
      )
      (libsource (lib "HCD_Database_Libs") (part "StandardResistor"))
    )
    (comp (ref "R31")
      (value "62R")
      (footprint "R_0805_L")
      (fields
        (field (name "TOLERANCE") "±1%")
        (field (name "PACKAGE") "805")
        (field (name "MANUFACTURER") "YAGEO")
        (field (name "POWER") "0,125W")
        (field (name "Comment") "StandardResistor")
      )
      (libsource (lib "HCD_Database_Libs") (part "StandardResistor"))
    )
    (comp (ref "R32")
      (value "10R")
      (footprint "R_0805_L")
      (description "10 Ohms ±1% 0.125W, 1/8W Chip Resistor 0805 (2012 Metric) Moisture Resistant Thick Film")
      (fields
        (field (name "TOLERANCE") "±1%")
        (field (name "PACKAGE") "805")
        (field (name "MANUFACTURER") "YAGEO")
        (field (name "POWER") "0,125W")
      )
      (libsource (lib "HCD_Database_Libs") (part "StandardResistor"))
    )
    (comp (ref "R33")
      (value "4K7")
      (footprint "R_0805_L")
      (description "4.7 kOhms ±1% 0.125W, 1/8W Chip Resistor 0805 (2012 Metric) Moisture Resistant Thick Film")
      (fields
        (field (name "TOLERANCE") "±1%")
        (field (name "PACKAGE") "805")
        (field (name "MANUFACTURER") "YAGEO")
        (field (name "POWER") "0,125W")
      )
      (libsource (lib "HCD_Database_Libs") (part "StandardResistor"))
    )
    (comp (ref "SW1")
      (value "BUTTON_2PIN")
      (footprint "BUTTON_DTSMF-31R-V_DIPTRONICS")
      (description "SWITCH TACT 6.00x3.50 4.30mm 260gF SMT V/T")
      (fields (field (name "MANUFACTURER") "DIPTRONICS") (field (name "VOLTAGE") "12V"))
      (libsource (lib "HCD_Database_Libs") (part "BUTTON_2PIN"))
    )
    (comp (ref "TP1")
      (value "~")
      (footprint "TP_SMD_CIRC_D1.0")
      (description "SMD CIRC Test Point 1mm")
      (libsource (lib "HCD_Database_Libs") (part "TP_1-PIN_CIRC_NO_BOM"))
    )
    (comp (ref "TP2")
      (value "~")
      (footprint "TP_SMD_CIRC_D1.0")
      (description "SMD CIRC Test Point 1mm")
      (libsource (lib "HCD_Database_Libs") (part "TP_1-PIN_CIRC_NO_BOM"))
    )
    (comp (ref "TP3")
      (value "~")
      (footprint "TP_SMD_CIRC_D1.0")
      (description "SMD CIRC Test Point 1mm")
      (libsource (lib "HCD_Database_Libs") (part "TP_1-PIN_CIRC_NO_BOM"))
    )
    (comp (ref "TP4")
      (value "~")
      (footprint "TP_SMD_CIRC_D1.0")
      (description "SMD CIRC Test Point 1mm")
      (libsource (lib "HCD_Database_Libs") (part "TP_1-PIN_CIRC_NO_BOM"))
    )
    (comp (ref "TP5")
      (value "~")
      (footprint "TP_SMD_CIRC_D1.0")
      (description "SMD CIRC Test Point 1mm")
      (libsource (lib "HCD_Database_Libs") (part "TP_1-PIN_CIRC_NO_BOM"))
    )
    (comp (ref "TVS1")
      (value "TVSDiodeUnidir_A1C2")
      (footprint "TVS_SMA_PANJIT")
      (description "DIODE TVS 400W 30V SMA")
      (fields
        (field (name "VOLTAGE") "30V")
        (field (name "CURRENT") "8.3A")
        (field (name "PACKAGE") "DO214AC")
        (field (name "MANUFACTURER") "PANJIT")
      )
      (libsource (lib "HCD_Database_Libs") (part "TVSDiodeUnidir_A1C2"))
    )
  )
  (nets
    (net (code "1") (name "+3V3") (class "Default")
      (node (ref "C12") (pin "1") (pinfunction "1_1") (pintype "passive"))
      (node (ref "C13") (pin "2") (pinfunction "2_2") (pintype "passive"))
      (node (ref "C14") (pin "2") (pinfunction "2_2") (pintype "passive"))
      (node (ref "C15") (pin "1") (pinfunction "1_1") (pintype "passive"))
      (node (ref "C16") (pin "1") (pinfunction "1_1") (pintype "passive"))
      (node (ref "C19") (pin "2") (pinfunction "2_2") (pintype "passive"))
      (node (ref "C20") (pin "2") (pinfunction "2_2") (pintype "passive"))
      (node (ref "C22") (pin "1") (pinfunction "1_1") (pintype "passive"))
      (node (ref "C23") (pin "1") (pinfunction "1_1") (pintype "passive"))
      (node (ref "C29") (pin "2") (pinfunction "2_2") (pintype "passive"))
      (node (ref "C4") (pin "1") (pinfunction "1_1") (pintype "passive"))
      (node (ref "C6") (pin "2") (pinfunction "2_2") (pintype "passive"))
      (node (ref "CON2") (pin "1") (pinfunction "0_1") (pintype "passive"))
      (node (ref "IC1") (pin "2") (pinfunction "Vout_2") (pintype "passive"))
      (node (ref "IC3") (pin "24") (pinfunction "VDD_24") (pintype "passive"))
      (node (ref "IC3") (pin "36") (pinfunction "VDDIO2_36") (pintype "passive"))
      (node (ref "IC3") (pin "48") (pinfunction "VDD_48") (pintype "passive"))
      (node (ref "IC3") (pin "9") (pinfunction "VDDA_9") (pintype "passive"))
      (node (ref "IC5") (pin "5") (pinfunction "VCC_5") (pintype "passive"))
      (node (ref "IC6") (pin "1") (pinfunction "VCC1_1") (pintype "passive"))
      (node (ref "R12") (pin "2") (pinfunction "2_2") (pintype "passive"))
      (node (ref "R13") (pin "2") (pinfunction "2_2") (pintype "passive"))
      (node (ref "R16") (pin "2") (pinfunction "2_2") (pintype "passive"))
      (node (ref "R23") (pin "2") (pinfunction "2_2") (pintype "passive"))
    )
    (net (code "2") (name "+5V") (class "Default")
      (node (ref "C11") (pin "1") (pinfunction "1_1") (pintype "passive"))
      (node (ref "C2") (pin "1") (pinfunction "1_1") (pintype "passive"))
      (node (ref "C24") (pin "1") (pinfunction "1_1") (pintype "passive"))
      (node (ref "C25") (pin "2") (pinfunction "2_2") (pintype "passive"))
      (node (ref "C26") (pin "2") (pinfunction "2_2") (pintype "passive"))
      (node (ref "C3") (pin "2") (pinfunction "2_2") (pintype "passive"))
      (node (ref "C32") (pin "1") (pinfunction "1_1") (pintype "passive"))
      (node (ref "C5") (pin "2") (pinfunction "2_2") (pintype "passive"))
      (node (ref "IC1") (pin "3") (pinfunction "Vin_3") (pintype "passive"))
      (node (ref "IC4") (pin "8") (pinfunction "VCC_8") (pintype "passive"))
      (node (ref "IC7") (pin "20") (pinfunction "Vcc_20") (pintype "passive"))
      (node (ref "IC8") (pin "20") (pinfunction "Vcc_20") (pintype "passive"))
      (node (ref "L1") (pin "2") (pinfunction "2_2") (pintype "passive"))
      (node (ref "MDL1") (pin "2") (pinfunction "+Vin_2") (pintype "passive"))
      (node (ref "R1") (pin "2") (pinfunction "2_2") (pintype "passive"))
      (node (ref "R20") (pin "1") (pinfunction "1_1") (pintype "passive"))
      (node (ref "TP1") (pin "1") (pinfunction "1_1") (pintype "passive"))
    )
    (net (code "3") (name "+5V_ISO") (class "Default")
      (node (ref "C28") (pin "2") (pinfunction "2_2") (pintype "passive"))
      (node (ref "C30") (pin "2") (pinfunction "2_2") (pintype "passive"))
      (node (ref "C31") (pin "2") (pinfunction "2_2") (pintype "passive"))
      (node (ref "IC6") (pin "8") (pinfunction "VCC2_8") (pintype "passive"))
      (node (ref "MDL1") (pin "5") (pinfunction "+Vout_5") (pintype "passive"))
      (node (ref "R24") (pin "2") (pinfunction "2_2") (pintype "passive"))
      (node (ref "R26") (pin "2") (pinfunction "2_2") (pintype "passive"))
      (node (ref "TP4") (pin "1") (pinfunction "1_1") (pintype "passive"))
    )
    (net (code "4") (name "+12V") (class "Default")
      (node (ref "C7") (pin "1") (pinfunction "1_1") (pintype "passive"))
      (node (ref "C8") (pin "2") (pinfunction "2_2") (pintype "passive"))
      (node (ref "CON1") (pin "14") (pinfunction "14_14") (pintype "passive"))
      (node (ref "CON1") (pin "15") (pinfunction "15_15") (pintype "passive"))
      (node (ref "CON1") (pin "16") (pinfunction "16_16") (pintype "passive"))
      (node (ref "D2") (pin "2") (pinfunction "C_2") (pintype "passive"))
      (node (ref "D4") (pin "2") (pinfunction "C_2") (pintype "passive"))
      (node (ref "IC2") (pin "2") (pinfunction "Vin_2") (pintype "passive"))
      (node (ref "R3") (pin "2") (pinfunction "2_2") (pintype "passive"))
      (node (ref "TP2") (pin "1") (pinfunction "1_1") (pintype "passive"))
      (node (ref "TVS1") (pin "2") (pinfunction "C_2") (pintype "passive"))
    )
    (net (code "5") (name "+12V_SPLY") (class "Default")
      (node (ref "CON3") (pin "5") (pinfunction "5_5") (pintype "passive"))
      (node (ref "D2") (pin "1") (pinfunction "A_1") (pintype "passive"))
      (node (ref "D4") (pin "1") (pinfunction "A_1") (pintype "passive"))
    )
    (net (code "6") (name "/BLINK_1") (class "Default")
      (node (ref "IC3") (pin "11") (pinfunction "PA1_11") (pintype "passive"))
      (node (ref "R29") (pin "2") (pinfunction "2_2") (pintype "passive"))
    )
    (net (code "7") (name "/BLINK_2") (class "Default")
      (node (ref "IC3") (pin "10") (pinfunction "PA0_10") (pintype "passive"))
      (node (ref "R30") (pin "2") (pinfunction "2_2") (pintype "passive"))
    )
    (net (code "8") (name "/BOOT0") (class "Default")
      (node (ref "CON4") (pin "2") (pinfunction "2_2") (pintype "passive"))
      (node (ref "IC3") (pin "44") (pinfunction "BOOT0_44") (pintype "passive"))
      (node (ref "R21") (pin "2") (pinfunction "2_2") (pintype "passive"))
    )
    (net (code "9") (name "/CAN_H") (class "Default")
      (node (ref "CON1") (pin "11") (pinfunction "11_11") (pintype "passive"))
      (node (ref "CON3") (pin "6") (pinfunction "6_6") (pintype "passive"))
      (node (ref "R22") (pin "1") (pinfunction "1_1") (pintype "passive"))
    )
    (net (code "10") (name "/CAN_L") (class "Default")
      (node (ref "CON1") (pin "12") (pinfunction "12_12") (pintype "passive"))
      (node (ref "CON3") (pin "7") (pinfunction "7_7") (pintype "passive"))
      (node (ref "R32") (pin "1") (pinfunction "1_1") (pintype "passive"))
    )
    (net (code "11") (name "/CAN_RX") (class "Default")
      (node (ref "IC3") (pin "45") (pinfunction "PB8_45") (pintype "passive"))
      (node (ref "IC6") (pin "2") (pinfunction "RXD_2") (pintype "passive"))
      (node (ref "R23") (pin "1") (pinfunction "1_1") (pintype "passive"))
    )
    (net (code "12") (name "/CAN_TX") (class "Default")
      (node (ref "IC3") (pin "46") (pinfunction "PB9_46") (pintype "passive"))
      (node (ref "IC6") (pin "3") (pinfunction "TXD_3") (pintype "passive"))
    )
    (net (code "13") (name "/FB") (class "Default")
      (node (ref "IC2") (pin "5") (pinfunction "FB_5") (pintype "passive"))
      (node (ref "R1") (pin "1") (pinfunction "1_1") (pintype "passive"))
      (node (ref "R2") (pin "2") (pinfunction "2_2") (pintype "passive"))
    )
    (net (code "14") (name "/FLYBACK_EN") (class "Default")
      (node (ref "IC3") (pin "12") (pinfunction "PA2_12") (pintype "passive"))
      (node (ref "IC7") (pin "6") (pinfunction "1A3_6") (pintype "passive"))
      (node (ref "R28") (pin "2") (pinfunction "2_2") (pintype "passive"))
    )
    (net (code "15") (name "/FLY_EN") (class "Default")
      (node (ref "CON1") (pin "20") (pinfunction "20_20") (pintype "passive"))
      (node (ref "IC7") (pin "14") (pinfunction "1Y3_14") (pintype "passive"))
    )
    (net (code "16") (name "/INRS1") (class "Default")
      (node (ref "CON1") (pin "10") (pinfunction "10_10") (pintype "passive"))
      (node (ref "IC7") (pin "18") (pinfunction "1Y1_18") (pintype "passive"))
    )
    (net (code "17") (name "/INRS1_MCU") (class "Default")
      (node (ref "IC3") (pin "18") (pinfunction "PB0_18") (pintype "passive"))
      (node (ref "IC7") (pin "2") (pinfunction "1A1_2") (pintype "passive"))
    )
    (net (code "18") (name "/INRS2") (class "Default")
      (node (ref "CON1") (pin "9") (pinfunction "9_9") (pintype "passive"))
      (node (ref "IC7") (pin "16") (pinfunction "1Y2_16") (pintype "passive"))
    )
    (net (code "19") (name "/INRS2_MCU") (class "Default")
      (node (ref "IC3") (pin "17") (pinfunction "PA7_17") (pintype "passive"))
      (node (ref "IC7") (pin "4") (pinfunction "1A2_4") (pintype "passive"))
    )
    (net (code "20") (name "/MODBUS_RX") (class "Default")
      (node (ref "IC3") (pin "31") (pinfunction "PA10_31") (pintype "passive"))
      (node (ref "IC4") (pin "1") (pinfunction "R_1") (pintype "passive"))
      (node (ref "R12") (pin "1") (pinfunction "1_1") (pintype "passive"))
    )
    (net (code "21") (name "/MODBUS_TX") (class "Default")
      (node (ref "D3") (pin "1") (pinfunction "A_1") (pintype "passive"))
      (node (ref "IC3") (pin "30") (pinfunction "PA9_30") (pintype "passive"))
      (node (ref "IC4") (pin "4") (pinfunction "D_4") (pintype "passive"))
      (node (ref "R15") (pin "2") (pinfunction "2_2") (pintype "passive"))
      (node (ref "R19") (pin "2") (pinfunction "2_2") (pintype "passive"))
    )
    (net (code "22") (name "/NRST") (class "Default")
      (node (ref "C18") (pin "2") (pinfunction "2_2") (pintype "passive"))
      (node (ref "CON2") (pin "5") (pinfunction "0_5") (pintype "passive"))
      (node (ref "IC3") (pin "7") (pinfunction "NRST_7") (pintype "passive"))
      (node (ref "R16") (pin "1") (pinfunction "1_1") (pintype "passive"))
      (node (ref "SW1") (pin "1") (pinfunction "1_1") (pintype "passive"))
    )
    (net (code "23") (name "/PHS_N_OFF") (class "Default")
      (node (ref "CON1") (pin "4") (pinfunction "4_4") (pintype "passive"))
      (node (ref "IC8") (pin "3") (pinfunction "2Y4_3") (pintype "passive"))
    )
    (net (code "24") (name "/PHS_N_OFF_MCU") (class "Default")
      (node (ref "IC3") (pin "19") (pinfunction "PB1_19") (pintype "passive"))
      (node (ref "IC8") (pin "17") (pinfunction "2A4_17") (pintype "passive"))
    )
    (net (code "25") (name "/PHS_N_ON") (class "Default")
      (node (ref "CON1") (pin "3") (pinfunction "3_3") (pintype "passive"))
      (node (ref "IC8") (pin "5") (pinfunction "2Y3_5") (pintype "passive"))
    )
    (net (code "26") (name "/PHS_N_ON_MCU") (class "Default")
      (node (ref "IC3") (pin "20") (pinfunction "PB2_20") (pintype "passive"))
      (node (ref "IC8") (pin "15") (pinfunction "2A3_15") (pintype "passive"))
    )
    (net (code "27") (name "/PHS_R_OFF") (class "Default")
      (node (ref "CON1") (pin "7") (pinfunction "7_7") (pintype "passive"))
      (node (ref "IC8") (pin "16") (pinfunction "1Y2_16") (pintype "passive"))
    )
    (net (code "28") (name "/PHS_R_OFF_MCU") (class "Default")
      (node (ref "IC3") (pin "15") (pinfunction "PA5_15") (pintype "passive"))
      (node (ref "IC8") (pin "4") (pinfunction "1A2_4") (pintype "passive"))
    )
    (net (code "29") (name "/PHS_R_ON") (class "Default")
      (node (ref "CON1") (pin "8") (pinfunction "8_8") (pintype "passive"))
      (node (ref "IC8") (pin "18") (pinfunction "1Y1_18") (pintype "passive"))
    )
    (net (code "30") (name "/PHS_R_ON_MCU") (class "Default")
      (node (ref "IC3") (pin "16") (pinfunction "PA6_16") (pintype "passive"))
      (node (ref "IC8") (pin "2") (pinfunction "1A1_2") (pintype "passive"))
    )
    (net (code "31") (name "/PHS_S_OFF") (class "Default")
      (node (ref "CON1") (pin "5") (pinfunction "5_5") (pintype "passive"))
      (node (ref "IC8") (pin "12") (pinfunction "1Y4_12") (pintype "passive"))
    )
    (net (code "32") (name "/PHS_S_OFF_MCU") (class "Default")
      (node (ref "IC3") (pin "13") (pinfunction "PA3_13") (pintype "passive"))
      (node (ref "IC8") (pin "8") (pinfunction "1A4_8") (pintype "passive"))
    )
    (net (code "33") (name "/PHS_S_ON") (class "Default")
      (node (ref "CON1") (pin "6") (pinfunction "6_6") (pintype "passive"))
      (node (ref "IC8") (pin "14") (pinfunction "1Y3_14") (pintype "passive"))
    )
    (net (code "34") (name "/PHS_S_ON_MCU") (class "Default")
      (node (ref "IC3") (pin "14") (pinfunction "PA4_14") (pintype "passive"))
      (node (ref "IC8") (pin "6") (pinfunction "1A3_6") (pintype "passive"))
    )
    (net (code "35") (name "/PHS_T_OFF") (class "Default")
      (node (ref "CON1") (pin "2") (pinfunction "2_2") (pintype "passive"))
      (node (ref "IC8") (pin "7") (pinfunction "2Y2_7") (pintype "passive"))
    )
    (net (code "36") (name "/PHS_T_OFF_MCU") (class "Default")
      (node (ref "IC3") (pin "26") (pinfunction "PB13_26") (pintype "passive"))
      (node (ref "IC8") (pin "13") (pinfunction "2A2_13") (pintype "passive"))
    )
    (net (code "37") (name "/PHS_T_ON") (class "Default")
      (node (ref "CON1") (pin "1") (pinfunction "1_1") (pintype "passive"))
      (node (ref "IC8") (pin "9") (pinfunction "2Y1_9") (pintype "passive"))
    )
    (net (code "38") (name "/PHS_T_ON_MCU") (class "Default")
      (node (ref "IC3") (pin "25") (pinfunction "PB12_25") (pintype "passive"))
      (node (ref "IC8") (pin "11") (pinfunction "2A1_11") (pintype "passive"))
    )
    (net (code "39") (name "/RS485_A") (class "Default")
      (node (ref "CON3") (pin "1") (pinfunction "1_1") (pintype "passive"))
      (node (ref "R17") (pin "1") (pinfunction "1_1") (pintype "passive"))
      (node (ref "R18") (pin "1") (pinfunction "1_1") (pintype "passive"))
    )
    (net (code "40") (name "/RS485_B") (class "Default")
      (node (ref "CON3") (pin "2") (pinfunction "2_2") (pintype "passive"))
      (node (ref "R11") (pin "1") (pinfunction "1_1") (pintype "passive"))
      (node (ref "R17") (pin "2") (pinfunction "2_2") (pintype "passive"))
    )
    (net (code "41") (name "/SWCLK") (class "Default")
      (node (ref "CON2") (pin "2") (pinfunction "0_2") (pintype "passive"))
      (node (ref "IC3") (pin "37") (pinfunction "PA14_37") (pintype "passive"))
    )
    (net (code "42") (name "/SWDIO") (class "Default")
      (node (ref "CON2") (pin "4") (pinfunction "0_4") (pintype "passive"))
      (node (ref "IC3") (pin "34") (pinfunction "PA13_34") (pintype "passive"))
    )
    (net (code "43") (name "GND") (class "Default")
      (node (ref "C10") (pin "1") (pinfunction "1_1") (pintype "passive"))
      (node (ref "C11") (pin "2") (pinfunction "2_2") (pintype "passive"))
      (node (ref "C12") (pin "2") (pinfunction "2_2") (pintype "passive"))
      (node (ref "C13") (pin "1") (pinfunction "1_1") (pintype "passive"))
      (node (ref "C14") (pin "1") (pinfunction "1_1") (pintype "passive"))
      (node (ref "C15") (pin "2") (pinfunction "2_2") (pintype "passive"))
      (node (ref "C16") (pin "2") (pinfunction "2_2") (pintype "passive"))
      (node (ref "C17") (pin "1") (pinfunction "1_1") (pintype "passive"))
      (node (ref "C18") (pin "1") (pinfunction "1_1") (pintype "passive"))
      (node (ref "C19") (pin "1") (pinfunction "1_1") (pintype "passive"))
      (node (ref "C2") (pin "2") (pinfunction "2_2") (pintype "passive"))
      (node (ref "C20") (pin "1") (pinfunction "1_1") (pintype "passive"))
      (node (ref "C21") (pin "1") (pinfunction "1_1") (pintype "passive"))
      (node (ref "C22") (pin "2") (pinfunction "2_2") (pintype "passive"))
      (node (ref "C23") (pin "2") (pinfunction "2_2") (pintype "passive"))
      (node (ref "C24") (pin "2") (pinfunction "2_2") (pintype "passive"))
      (node (ref "C25") (pin "1") (pinfunction "1_1") (pintype "passive"))
      (node (ref "C26") (pin "1") (pinfunction "1_1") (pintype "passive"))
      (node (ref "C29") (pin "1") (pinfunction "1_1") (pintype "passive"))
      (node (ref "C3") (pin "1") (pinfunction "1_1") (pintype "passive"))
      (node (ref "C32") (pin "2") (pinfunction "2_2") (pintype "passive"))
      (node (ref "C4") (pin "2") (pinfunction "2_2") (pintype "passive"))
      (node (ref "C5") (pin "1") (pinfunction "1_1") (pintype "passive"))
      (node (ref "C6") (pin "1") (pinfunction "1_1") (pintype "passive"))
      (node (ref "C7") (pin "2") (pinfunction "2_2") (pintype "passive"))
      (node (ref "C8") (pin "1") (pinfunction "1_1") (pintype "passive"))
      (node (ref "C9") (pin "1") (pinfunction "1_1") (pintype "passive"))
      (node (ref "CON1") (pin "17") (pinfunction "17_17") (pintype "passive"))
      (node (ref "CON1") (pin "18") (pinfunction "18_18") (pintype "passive"))
      (node (ref "CON1") (pin "19") (pinfunction "19_19") (pintype "passive"))
      (node (ref "CON2") (pin "3") (pinfunction "0_3") (pintype "passive"))
      (node (ref "CON3") (pin "4") (pinfunction "4_4") (pintype "passive"))
      (node (ref "D1") (pin "1") (pinfunction "A_1") (pintype "passive"))
      (node (ref "IC1") (pin "1") (pinfunction "GND_1") (pintype "passive"))
      (node (ref "IC2") (pin "7") (pinfunction "GND_7") (pintype "passive"))
      (node (ref "IC2") (pin "9") (pinfunction "PWRPD_9") (pintype "passive"))
      (node (ref "IC3") (pin "23") (pinfunction "VSS_23") (pintype "passive"))
      (node (ref "IC3") (pin "35") (pinfunction "VSS_35") (pintype "passive"))
      (node (ref "IC3") (pin "47") (pinfunction "VSS_47") (pintype "passive"))
      (node (ref "IC3") (pin "8") (pinfunction "VSSA_8") (pintype "passive"))
      (node (ref "IC4") (pin "5") (pinfunction "GND_5") (pintype "passive"))
      (node (ref "IC5") (pin "3") (pinfunction "GND_3") (pintype "passive"))
      (node (ref "IC6") (pin "4") (pinfunction "GND1_4") (pintype "passive"))
      (node (ref "IC7") (pin "1") (pinfunction "1~{OE}_1") (pintype "passive"))
      (node (ref "IC7") (pin "10") (pinfunction "GND_10") (pintype "passive"))
      (node (ref "IC7") (pin "19") (pinfunction "2~{OE}_19") (pintype "passive"))
      (node (ref "IC8") (pin "1") (pinfunction "1~{OE}_1") (pintype "passive"))
      (node (ref "IC8") (pin "10") (pinfunction "GND_10") (pintype "passive"))
      (node (ref "IC8") (pin "19") (pinfunction "2~{OE}_19") (pintype "passive"))
      (node (ref "LED2") (pin "2") (pinfunction "C_2") (pintype "passive"))
      (node (ref "LED3") (pin "2") (pinfunction "C_2") (pintype "passive"))
      (node (ref "LED4") (pin "2") (pinfunction "C_2") (pintype "passive"))
      (node (ref "MDL1") (pin "1") (pinfunction "-Vin_1") (pintype "passive"))
      (node (ref "R14") (pin "2") (pinfunction "2_2") (pintype "passive"))
      (node (ref "R21") (pin "1") (pinfunction "1_1") (pintype "passive"))
      (node (ref "R6") (pin "1") (pinfunction "1_1") (pintype "passive"))
      (node (ref "R7") (pin "1") (pinfunction "1_1") (pintype "passive"))
      (node (ref "R8") (pin "1") (pinfunction "1_1") (pintype "passive"))
      (node (ref "R9") (pin "2") (pinfunction "2_2") (pintype "passive"))
      (node (ref "SW1") (pin "2") (pinfunction "2_2") (pintype "passive"))
      (node (ref "TP3") (pin "1") (pinfunction "1_1") (pintype "passive"))
      (node (ref "TVS1") (pin "1") (pinfunction "A_1") (pintype "passive"))
    )
    (net (code "44") (name "GND_ISO") (class "Default")
      (node (ref "C27") (pin "1") (pinfunction "1_1") (pintype "passive"))
      (node (ref "C28") (pin "1") (pinfunction "1_1") (pintype "passive"))
      (node (ref "C30") (pin "1") (pinfunction "1_1") (pintype "passive"))
      (node (ref "C31") (pin "1") (pinfunction "1_1") (pintype "passive"))
      (node (ref "CON1") (pin "13") (pinfunction "13_13") (pintype "passive"))
      (node (ref "IC6") (pin "5") (pinfunction "GND2_5") (pintype "passive"))
      (node (ref "LED1") (pin "2") (pinfunction "C_2") (pintype "passive"))
      (node (ref "MDL1") (pin "4") (pinfunction "-Vout_4") (pintype "passive"))
      (node (ref "R10") (pin "2") (pinfunction "2_2") (pintype "passive"))
      (node (ref "R33") (pin "1") (pinfunction "1_1") (pintype "passive"))
      (node (ref "TP5") (pin "1") (pinfunction "1_1") (pintype "passive"))
    )
    (net (code "45") (name "Net-(C10-Pad2)") (class "Default")
      (node (ref "C10") (pin "2") (pinfunction "2_2") (pintype "passive"))
      (node (ref "R4") (pin "1") (pinfunction "1_1") (pintype "passive"))
    )
    (net (code "46") (name "Net-(C21-Pad2)") (class "Default")
      (node (ref "C21") (pin "2") (pinfunction "2_2") (pintype "passive"))
      (node (ref "R19") (pin "1") (pinfunction "1_1") (pintype "passive"))
    )
    (net (code "47") (name "Net-(C27-Pad2)") (class "Default")
      (node (ref "C27") (pin "2") (pinfunction "2_2") (pintype "passive"))
      (node (ref "R25") (pin "1") (pinfunction "1_1") (pintype "passive"))
      (node (ref "R31") (pin "2") (pinfunction "2_2") (pintype "passive"))
    )
    (net (code "48") (name "Net-(CON3-Pad3)") (class "Default")
      (node (ref "CON3") (pin "3") (pinfunction "3_3") (pintype "passive"))
      (node (ref "R9") (pin "1") (pinfunction "1_1") (pintype "passive"))
    )
    (net (code "49") (name "Net-(CON3-Pad8)") (class "Default")
      (node (ref "CON3") (pin "8") (pinfunction "8_8") (pintype "passive"))
      (node (ref "R10") (pin "1") (pinfunction "1_1") (pintype "passive"))
    )
    (net (code "50") (name "Net-(CON4-Pad1)") (class "Default")
      (node (ref "CON4") (pin "1") (pinfunction "1_1") (pintype "passive"))
      (node (ref "R13") (pin "1") (pinfunction "1_1") (pintype "passive"))
    )
    (net (code "51") (name "Net-(D1-C)") (class "Default")
      (node (ref "C1") (pin "2") (pinfunction "2_2") (pintype "passive"))
      (node (ref "D1") (pin "2") (pinfunction "C_2") (pintype "passive"))
      (node (ref "IC2") (pin "8") (pinfunction "SW_8") (pintype "passive"))
      (node (ref "L1") (pin "1") (pinfunction "1_1") (pintype "passive"))
    )
    (net (code "52") (name "Net-(D3-C)") (class "Default")
      (node (ref "C17") (pin "2") (pinfunction "2_2") (pintype "passive"))
      (node (ref "D3") (pin "2") (pinfunction "C_2") (pintype "passive"))
      (node (ref "IC5") (pin "2") (pinfunction "A_2") (pintype "passive"))
      (node (ref "R15") (pin "1") (pinfunction "1_1") (pintype "passive"))
    )
    (net (code "53") (name "Net-(IC2-BOOT)") (class "Default")
      (node (ref "C1") (pin "1") (pinfunction "1_1") (pintype "passive"))
      (node (ref "IC2") (pin "1") (pinfunction "BOOT_1") (pintype "passive"))
    )
    (net (code "54") (name "Net-(IC2-COMP)") (class "Default")
      (node (ref "C9") (pin "2") (pinfunction "2_2") (pintype "passive"))
      (node (ref "IC2") (pin "6") (pinfunction "COMP_6") (pintype "passive"))
      (node (ref "R4") (pin "2") (pinfunction "2_2") (pintype "passive"))
    )
    (net (code "55") (name "Net-(IC2-EN)") (class "Default")
      (node (ref "IC2") (pin "3") (pinfunction "EN_3") (pintype "passive"))
      (node (ref "R5") (pin "1") (pinfunction "1_1") (pintype "passive"))
      (node (ref "R8") (pin "2") (pinfunction "2_2") (pintype "passive"))
    )
    (net (code "56") (name "Net-(IC2-RT{slash}CLK)") (class "Default")
      (node (ref "IC2") (pin "4") (pinfunction "RT/CLK_4") (pintype "passive"))
      (node (ref "R6") (pin "2") (pinfunction "2_2") (pintype "passive"))
    )
    (net (code "57") (name "Net-(IC4-A)") (class "Default")
      (node (ref "IC4") (pin "6") (pinfunction "A_6") (pintype "passive"))
      (node (ref "R18") (pin "2") (pinfunction "2_2") (pintype "passive"))
      (node (ref "R20") (pin "2") (pinfunction "2_2") (pintype "passive"))
    )
    (net (code "58") (name "Net-(IC4-B)") (class "Default")
      (node (ref "IC4") (pin "7") (pinfunction "B_7") (pintype "passive"))
      (node (ref "R11") (pin "2") (pinfunction "2_2") (pintype "passive"))
      (node (ref "R14") (pin "1") (pinfunction "1_1") (pintype "passive"))
    )
    (net (code "59") (name "Net-(IC4-DE)") (class "Default")
      (node (ref "IC4") (pin "2") (pinfunction "~{RE}_2") (pintype "passive"))
      (node (ref "IC4") (pin "3") (pinfunction "DE_3") (pintype "passive"))
      (node (ref "IC5") (pin "4") (pinfunction "Y_4") (pintype "passive"))
    )
    (net (code "60") (name "Net-(IC6-CANH)") (class "Default")
      (node (ref "IC6") (pin "7") (pinfunction "CANH_7") (pintype "passive"))
      (node (ref "R22") (pin "2") (pinfunction "2_2") (pintype "passive"))
      (node (ref "R24") (pin "1") (pinfunction "1_1") (pintype "passive"))
      (node (ref "R25") (pin "2") (pinfunction "2_2") (pintype "passive"))
    )
    (net (code "61") (name "Net-(IC6-CANL)") (class "Default")
      (node (ref "IC6") (pin "6") (pinfunction "CANL_6") (pintype "passive"))
      (node (ref "R31") (pin "1") (pinfunction "1_1") (pintype "passive"))
      (node (ref "R32") (pin "2") (pinfunction "2_2") (pintype "passive"))
      (node (ref "R33") (pin "2") (pinfunction "2_2") (pintype "passive"))
    )
    (net (code "62") (name "Net-(LED1-A)") (class "Default")
      (node (ref "LED1") (pin "1") (pinfunction "A_1") (pintype "passive"))
      (node (ref "R26") (pin "1") (pinfunction "1_1") (pintype "passive"))
    )
    (net (code "63") (name "Net-(LED2-A)") (class "Default")
      (node (ref "LED2") (pin "1") (pinfunction "A_1") (pintype "passive"))
      (node (ref "R28") (pin "1") (pinfunction "1_1") (pintype "passive"))
    )
    (net (code "64") (name "Net-(LED3-A)") (class "Default")
      (node (ref "LED3") (pin "1") (pinfunction "A_1") (pintype "passive"))
      (node (ref "R29") (pin "1") (pinfunction "1_1") (pintype "passive"))
    )
    (net (code "65") (name "Net-(LED4-A)") (class "Default")
      (node (ref "LED4") (pin "1") (pinfunction "A_1") (pintype "passive"))
      (node (ref "R30") (pin "1") (pinfunction "1_1") (pintype "passive"))
    )
    (net (code "66") (name "Net-(R2-Pad1)") (class "Default")
      (node (ref "R2") (pin "1") (pinfunction "1_1") (pintype "passive"))
      (node (ref "R7") (pin "2") (pinfunction "2_2") (pintype "passive"))
    )
    (net (code "67") (name "Net-(R3-Pad1)") (class "Default")
      (node (ref "R3") (pin "1") (pinfunction "1_1") (pintype "passive"))
      (node (ref "R5") (pin "2") (pinfunction "2_2") (pintype "passive"))
    )
    (net (code "68") (name "unconnected-(IC3-PA8-Pad29)") (class "Default")
      (node (ref "IC3") (pin "29") (pinfunction "PA8_29") (pintype "passive"))
    )
    (net (code "69") (name "unconnected-(IC3-PA11-Pad32)") (class "Default")
      (node (ref "IC3") (pin "32") (pinfunction "PA11_32") (pintype "passive"))
    )
    (net (code "70") (name "unconnected-(IC3-PA12-Pad33)") (class "Default")
      (node (ref "IC3") (pin "33") (pinfunction "PA12_33") (pintype "passive"))
    )
    (net (code "71") (name "unconnected-(IC3-PA15-Pad38)") (class "Default")
      (node (ref "IC3") (pin "38") (pinfunction "PA15_38") (pintype "passive"))
    )
    (net (code "72") (name "unconnected-(IC3-PB3-Pad39)") (class "Default")
      (node (ref "IC3") (pin "39") (pinfunction "PB3_39") (pintype "passive"))
    )
    (net (code "73") (name "unconnected-(IC3-PB4-Pad40)") (class "Default")
      (node (ref "IC3") (pin "40") (pinfunction "PB4_40") (pintype "passive"))
    )
    (net (code "74") (name "unconnected-(IC3-PB5-Pad41)") (class "Default")
      (node (ref "IC3") (pin "41") (pinfunction "PB5_41") (pintype "passive"))
    )
    (net (code "75") (name "unconnected-(IC3-PB6-Pad42)") (class "Default")
      (node (ref "IC3") (pin "42") (pinfunction "PB6_42") (pintype "passive"))
    )
    (net (code "76") (name "unconnected-(IC3-PB7-Pad43)") (class "Default")
      (node (ref "IC3") (pin "43") (pinfunction "PB7_43") (pintype "passive"))
    )
    (net (code "77") (name "unconnected-(IC3-PB10-Pad21)") (class "Default")
      (node (ref "IC3") (pin "21") (pinfunction "PB10_21") (pintype "passive"))
    )
    (net (code "78") (name "unconnected-(IC3-PB11-Pad22)") (class "Default")
      (node (ref "IC3") (pin "22") (pinfunction "PB11_22") (pintype "passive"))
    )
    (net (code "79") (name "unconnected-(IC3-PB14-Pad27)") (class "Default")
      (node (ref "IC3") (pin "27") (pinfunction "PB14_27") (pintype "passive"))
    )
    (net (code "80") (name "unconnected-(IC3-PB15-Pad28)") (class "Default")
      (node (ref "IC3") (pin "28") (pinfunction "PB15_28") (pintype "passive"))
    )
    (net (code "81") (name "unconnected-(IC3-PC13-Pad2)") (class "Default")
      (node (ref "IC3") (pin "2") (pinfunction "PC13_2") (pintype "passive"))
    )
    (net (code "82") (name "unconnected-(IC3-PC14-OSC32_IN-Pad3)") (class "Default")
      (node (ref "IC3") (pin "3") (pinfunction "PC14-OSC32_IN_3") (pintype "passive"))
    )
    (net (code "83") (name "unconnected-(IC3-PC15-OSC32_OUT-Pad4)") (class "Default")
      (node (ref "IC3") (pin "4") (pinfunction "PC15-OSC32_OUT_4") (pintype "passive"))
    )
    (net (code "84") (name "unconnected-(IC3-PF0-OSC_IN-Pad5)") (class "Default")
      (node (ref "IC3") (pin "5") (pinfunction "PF0-OSC_IN_5") (pintype "passive"))
    )
    (net (code "85") (name "unconnected-(IC3-PF1-OSC_OUT-Pad6)") (class "Default")
      (node (ref "IC3") (pin "6") (pinfunction "PF1-OSC_OUT_6") (pintype "passive"))
    )
    (net (code "86") (name "unconnected-(IC3-VBAT-Pad1)") (class "Default")
      (node (ref "IC3") (pin "1") (pinfunction "VBAT_1") (pintype "passive"))
    )
    (net (code "87") (name "unconnected-(IC7-1A4-Pad8)") (class "Default")
      (node (ref "IC7") (pin "8") (pinfunction "1A4_8") (pintype "passive+no_connect"))
    )
    (net (code "88") (name "unconnected-(IC7-1Y4-Pad12)") (class "Default")
      (node (ref "IC7") (pin "12") (pinfunction "1Y4_12") (pintype "passive+no_connect"))
    )
    (net (code "89") (name "unconnected-(IC7-2A1-Pad11)") (class "Default")
      (node (ref "IC7") (pin "11") (pinfunction "2A1_11") (pintype "passive+no_connect"))
    )
    (net (code "90") (name "unconnected-(IC7-2A2-Pad13)") (class "Default")
      (node (ref "IC7") (pin "13") (pinfunction "2A2_13") (pintype "passive+no_connect"))
    )
    (net (code "91") (name "unconnected-(IC7-2A3-Pad15)") (class "Default")
      (node (ref "IC7") (pin "15") (pinfunction "2A3_15") (pintype "passive+no_connect"))
    )
    (net (code "92") (name "unconnected-(IC7-2A4-Pad17)") (class "Default")
      (node (ref "IC7") (pin "17") (pinfunction "2A4_17") (pintype "passive+no_connect"))
    )
    (net (code "93") (name "unconnected-(IC7-2Y1-Pad9)") (class "Default")
      (node (ref "IC7") (pin "9") (pinfunction "2Y1_9") (pintype "passive+no_connect"))
    )
    (net (code "94") (name "unconnected-(IC7-2Y2-Pad7)") (class "Default")
      (node (ref "IC7") (pin "7") (pinfunction "2Y2_7") (pintype "passive+no_connect"))
    )
    (net (code "95") (name "unconnected-(IC7-2Y3-Pad5)") (class "Default")
      (node (ref "IC7") (pin "5") (pinfunction "2Y3_5") (pintype "passive+no_connect"))
    )
    (net (code "96") (name "unconnected-(IC7-2Y4-Pad3)") (class "Default")
      (node (ref "IC7") (pin "3") (pinfunction "2Y4_3") (pintype "passive+no_connect"))
    )
    (net (code "97") (name "unconnected-(MDL1-NC-Pad8)") (class "Default")
      (node (ref "MDL1") (pin "8") (pinfunction "NC_8") (pintype "passive+no_connect"))
    )
  )
)
